# design.net
KiCad netlist of a schematic drawn in EasyEDA Pro
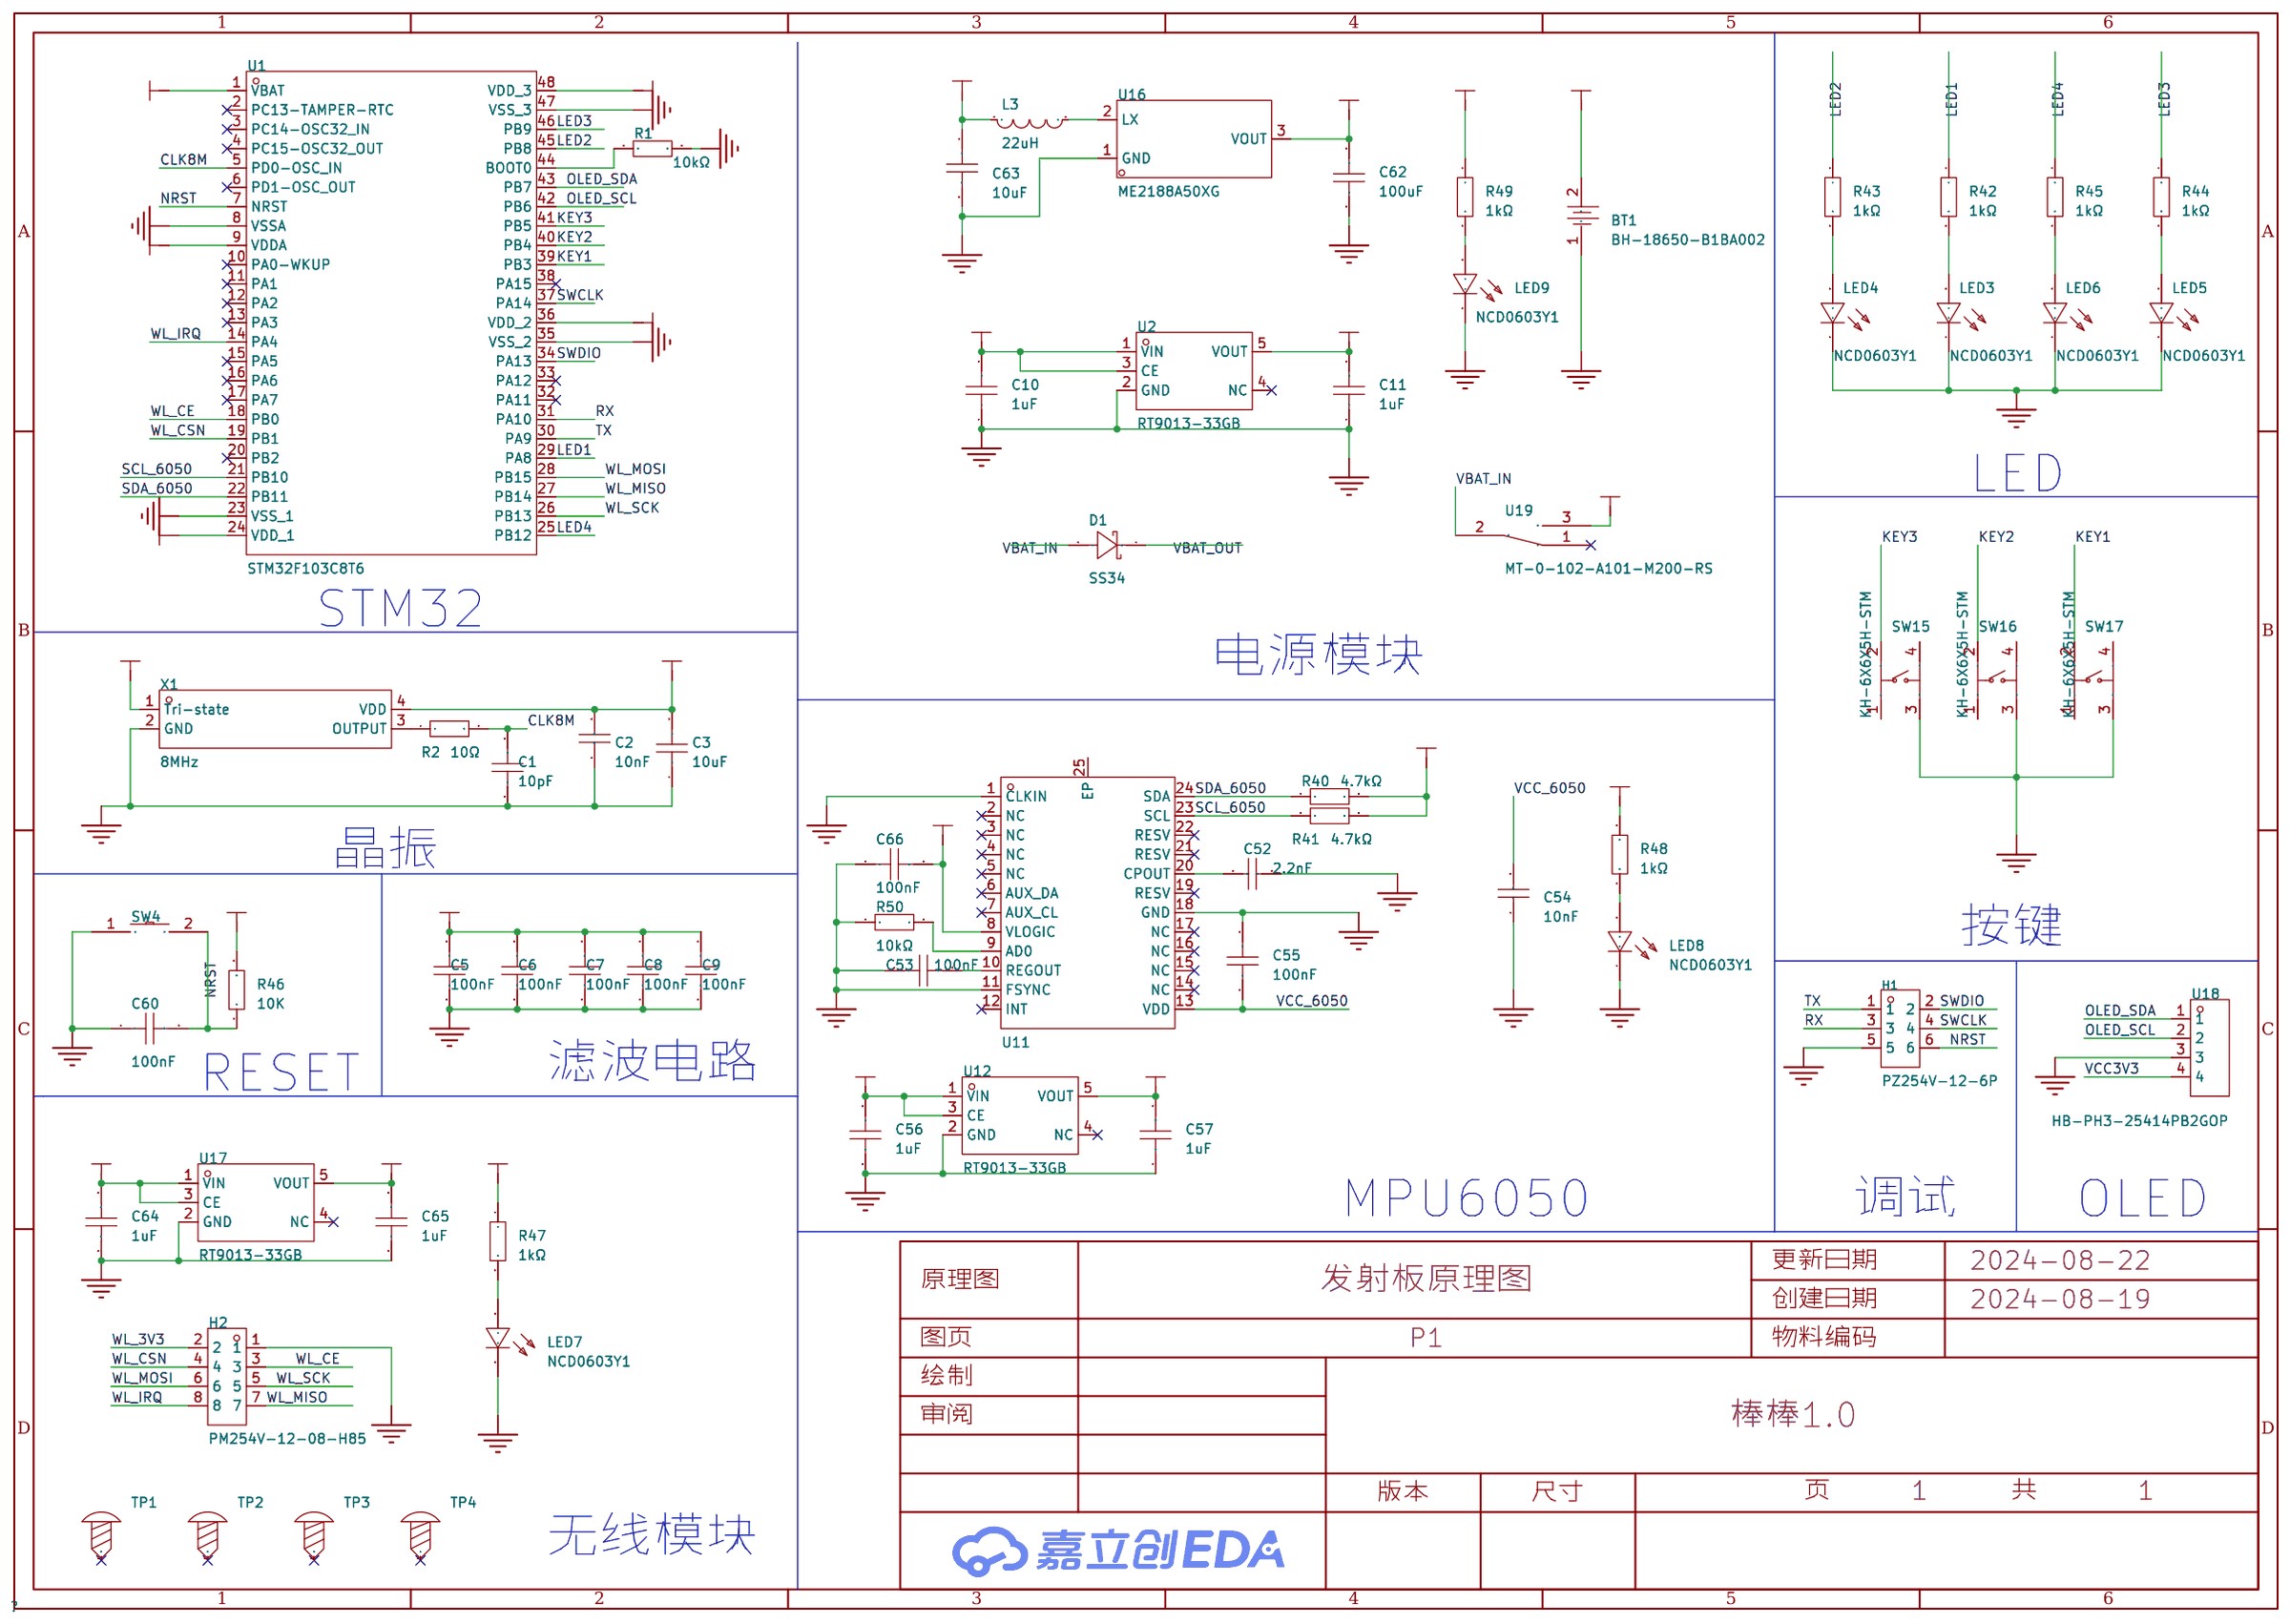
[diagram p0: schematic sheet]

(export (version "E")
  (design (tool "Eeschema 10.0.6"))
  (components
    (comp (ref "BT1")
      (value "BH-18650-B1BA002")
      (footprint "easyedapro:BATTERY-SMD_18650-1S-L77.1-W20.7-1")
      (description "连接器类型:电池盒;适用电池规格:18650;")
      (fields (field (name "Manufacturer") "MYOUNG(美阳)"))
      (libsource (lib "easyedapro") (part "BH-18650-B1BA002"))
    )
    (comp (ref "C1")
      (value "10pF")
      (footprint "easyedapro:C0603")
      (description "容值:10pF;精度:±5%;额定电压:50V;材质(温度系数):C0G;")
      (fields (field (name "Manufacturer Part") "0603CG100J500NT") (field (name "Manufacturer") "FH(风华)"))
      (libsource (lib "easyedapro") (part "0603CG100J500NT"))
    )
    (comp (ref "C2")
      (value "10nF")
      (footprint "easyedapro:C0603")
      (description "容值:10nF;精度:±10%;额定电压:50V;材质(温度系数):X7R;")
      (fields (field (name "Manufacturer Part") "0603B103K500NT") (field (name "Manufacturer") "FH(风华)"))
      (libsource (lib "easyedapro") (part "0603B103K500NT"))
    )
    (comp (ref "C3")
      (value "10uF")
      (footprint "easyedapro:C0603")
      (description "容值:10uF;精度:±10%;额定电压:10V;材质(温度系数):X5R;")
      (fields
        (field (name "Manufacturer Part") "CL10A106KP8NNNC")
        (field (name "Manufacturer") "SAMSUNG(三星)")
      )
      (libsource (lib "easyedapro") (part "CL10A106KP8NNNC"))
    )
    (comp (ref "C5")
      (value "100nF")
      (footprint "easyedapro:C0603")
      (description "容值:100nF;精度:±10%;额定电压:50V;材质(温度系数):X7R;")
      (fields
        (field (name "Manufacturer Part") "CC0603KRX7R9BB104")
        (field (name "Manufacturer") "YAGEO(国巨)")
      )
      (libsource (lib "easyedapro") (part "CC0603KRX7R9BB104"))
    )
    (comp (ref "C6")
      (value "100nF")
      (footprint "easyedapro:C0603")
      (description "容值:100nF;精度:±10%;额定电压:50V;材质(温度系数):X7R;")
      (fields
        (field (name "Manufacturer Part") "CC0603KRX7R9BB104")
        (field (name "Manufacturer") "YAGEO(国巨)")
      )
      (libsource (lib "easyedapro") (part "CC0603KRX7R9BB104"))
    )
    (comp (ref "C7")
      (value "100nF")
      (footprint "easyedapro:C0603")
      (description "容值:100nF;精度:±10%;额定电压:50V;材质(温度系数):X7R;")
      (fields
        (field (name "Manufacturer Part") "CC0603KRX7R9BB104")
        (field (name "Manufacturer") "YAGEO(国巨)")
      )
      (libsource (lib "easyedapro") (part "CC0603KRX7R9BB104"))
    )
    (comp (ref "C8")
      (value "100nF")
      (footprint "easyedapro:C0603")
      (description "容值:100nF;精度:±10%;额定电压:50V;材质(温度系数):X7R;")
      (fields
        (field (name "Manufacturer Part") "CC0603KRX7R9BB104")
        (field (name "Manufacturer") "YAGEO(国巨)")
      )
      (libsource (lib "easyedapro") (part "CC0603KRX7R9BB104"))
    )
    (comp (ref "C9")
      (value "100nF")
      (footprint "easyedapro:C0603")
      (description "容值:100nF;精度:±10%;额定电压:50V;材质(温度系数):X7R;")
      (fields
        (field (name "Manufacturer Part") "CC0603KRX7R9BB104")
        (field (name "Manufacturer") "YAGEO(国巨)")
      )
      (libsource (lib "easyedapro") (part "CC0603KRX7R9BB104"))
    )
    (comp (ref "C10")
      (value "1uF")
      (footprint "easyedapro:C0603")
      (description "容值:1uF;精度:±10%;额定电压:50V;材质(温度系数):X5R;")
      (fields
        (field (name "Manufacturer Part") "CL10A105KB8NNNC")
        (field (name "Manufacturer") "SAMSUNG(三星)")
      )
      (libsource (lib "easyedapro") (part "CL10A105KB8NNNC"))
    )
    (comp (ref "C11")
      (value "1uF")
      (footprint "easyedapro:C0603")
      (description "容值:1uF;精度:±10%;额定电压:50V;材质(温度系数):X5R;")
      (fields
        (field (name "Manufacturer Part") "CL10A105KB8NNNC")
        (field (name "Manufacturer") "SAMSUNG(三星)")
      )
      (libsource (lib "easyedapro") (part "CL10A105KB8NNNC"))
    )
    (comp (ref "C52")
      (value "2.2nF")
      (footprint "easyedapro:C0603")
      (description "容值:2.2nF;精度:±5%;额定电压:50V;材质(温度系数):X7R;")
      (fields (field (name "Manufacturer Part") "0603B222J500NT") (field (name "Manufacturer") "FH(风华)"))
      (libsource (lib "easyedapro") (part "0603B222J500NT"))
    )
    (comp (ref "C53")
      (value "100nF")
      (footprint "easyedapro:C0603")
      (description "容值:100nF;精度:±10%;额定电压:50V;材质(温度系数):X7R;")
      (fields
        (field (name "Manufacturer Part") "CC0603KRX7R9BB104")
        (field (name "Manufacturer") "YAGEO(国巨)")
      )
      (libsource (lib "easyedapro") (part "CC0603KRX7R9BB104"))
    )
    (comp (ref "C54")
      (value "10nF")
      (footprint "easyedapro:C0603")
      (description "容值:10nF;精度:±10%;额定电压:50V;材质(温度系数):X7R;")
      (fields
        (field (name "Manufacturer Part") "CC0603KRX7R9BB103")
        (field (name "Manufacturer") "YAGEO(国巨)")
      )
      (libsource (lib "easyedapro") (part "CC0603KRX7R9BB103"))
    )
    (comp (ref "C55")
      (value "100nF")
      (footprint "easyedapro:C0603")
      (description "容值:100nF;精度:±10%;额定电压:50V;材质(温度系数):X7R;")
      (fields
        (field (name "Manufacturer Part") "CC0603KRX7R9BB104")
        (field (name "Manufacturer") "YAGEO(国巨)")
      )
      (libsource (lib "easyedapro") (part "CC0603KRX7R9BB104"))
    )
    (comp (ref "C56")
      (value "1uF")
      (footprint "easyedapro:C0603")
      (description "容值:1uF;精度:±10%;额定电压:50V;材质(温度系数):X5R;")
      (fields
        (field (name "Manufacturer Part") "CL10A105KB8NNNC")
        (field (name "Manufacturer") "SAMSUNG(三星)")
      )
      (libsource (lib "easyedapro") (part "CL10A105KB8NNNC"))
    )
    (comp (ref "C57")
      (value "1uF")
      (footprint "easyedapro:C0603")
      (description "容值:1uF;精度:±10%;额定电压:50V;材质(温度系数):X5R;")
      (fields
        (field (name "Manufacturer Part") "CL10A105KB8NNNC")
        (field (name "Manufacturer") "SAMSUNG(三星)")
      )
      (libsource (lib "easyedapro") (part "CL10A105KB8NNNC"))
    )
    (comp (ref "C60")
      (value "100nF")
      (footprint "easyedapro:C0603")
      (libsource (lib "easyedapro") (part "CapAcitance"))
    )
    (comp (ref "C62")
      (value "100uF")
      (footprint "easyedapro:C0603")
      (libsource (lib "easyedapro") (part "CapAcitance"))
    )
    (comp (ref "C63")
      (value "10uF")
      (footprint "easyedapro:C0603")
      (libsource (lib "easyedapro") (part "CapAcitance"))
    )
    (comp (ref "C64")
      (value "1uF")
      (footprint "easyedapro:C0603")
      (description "容值:1uF;精度:±10%;额定电压:50V;材质(温度系数):X5R;")
      (fields
        (field (name "Manufacturer Part") "CL10A105KB8NNNC")
        (field (name "Manufacturer") "SAMSUNG(三星)")
      )
      (libsource (lib "easyedapro") (part "CL10A105KB8NNNC"))
    )
    (comp (ref "C65")
      (value "1uF")
      (footprint "easyedapro:C0603")
      (description "容值:1uF;精度:±10%;额定电压:50V;材质(温度系数):X5R;")
      (fields
        (field (name "Manufacturer Part") "CL10A105KB8NNNC")
        (field (name "Manufacturer") "SAMSUNG(三星)")
      )
      (libsource (lib "easyedapro") (part "CL10A105KB8NNNC"))
    )
    (comp (ref "C66")
      (value "100nF")
      (footprint "easyedapro:C0603")
      (description "容值:100nF;精度:±10%;额定电压:50V;材质(温度系数):X7R;")
      (fields
        (field (name "Manufacturer Part") "CC0603KRX7R9BB104")
        (field (name "Manufacturer") "YAGEO(国巨)")
      )
      (libsource (lib "easyedapro") (part "CC0603KRX7R9BB104"))
    )
    (comp (ref "D1")
      (value "SS34")
      (footprint "easyedapro:SMA_L4.3-W2.5-LS5.0-RD")
      (description "二极管配置:独立式;正向压降(Vf):550mV@3A;直流反向耐压(Vr):40V;平均整流电流(Io):3A;")
      (fields (field (name "Manufacturer") "TWGMC(台湾迪嘉)"))
      (libsource (lib "easyedapro") (part "SS34_C727060"))
    )
    (comp (ref "H1")
      (value "PZ254V-12-6P")
      (fields (field (name "Manufacturer") "XFCN(兴飞)"))
      (libsource (lib "easyedapro") (part "PZ254V-12-6P"))
    )
    (comp (ref "H2")
      (value "PM254V-12-08-H85")
      (footprint "easyedapro:HDR-TH_8P-P2.54-V-F-R2-C4-S2.54")
      (fields (field (name "Manufacturer") "XFCN(兴飞)"))
      (libsource (lib "easyedapro") (part "PM254V-12-08-H85_C2834799"))
    )
    (comp (ref "L3")
      (value "22uH")
      (footprint "easyedapro:IND-SMD_L7.1-W6.6")
      (description "电感值:22uH;精度:±20%;额定电流:3A;")
      (fields
        (field (name "Manufacturer Part") "YSPI0630A-220M")
        (field (name "Manufacturer") "YJYCOIN(益嘉源)")
      )
      (libsource (lib "easyedapro") (part "YSPI0630A-220M"))
    )
    (comp (ref "LED3")
      (value "NCD0603Y1")
      (footprint "easyedapro:LED0603-RD")
      (description "发光颜色:黄色;功率:65mW;透镜颜色:无色透明;主波长:586nm~595nm;发光强度:80mcd~220mcd;发光角度:130°;工作温度:-30°C~+85°C;")
      (fields (field (name "Manufacturer") "国星光电"))
      (libsource (lib "easyedapro") (part "FC-D1608HYK-588J"))
    )
    (comp (ref "LED4")
      (value "NCD0603Y1")
      (footprint "easyedapro:LED0603-RD")
      (description "发光颜色:黄色;功率:65mW;透镜颜色:无色透明;主波长:586nm~595nm;发光强度:80mcd~220mcd;发光角度:130°;工作温度:-30°C~+85°C;")
      (fields (field (name "Manufacturer") "国星光电"))
      (libsource (lib "easyedapro") (part "FC-D1608HYK-588J"))
    )
    (comp (ref "LED5")
      (value "NCD0603Y1")
      (footprint "easyedapro:LED0603-RD")
      (description "发光颜色:黄色;功率:65mW;透镜颜色:无色透明;主波长:586nm~595nm;发光强度:80mcd~220mcd;发光角度:130°;工作温度:-30°C~+85°C;")
      (fields (field (name "Manufacturer") "国星光电"))
      (libsource (lib "easyedapro") (part "FC-D1608HYK-588J"))
    )
    (comp (ref "LED6")
      (value "NCD0603Y1")
      (footprint "easyedapro:LED0603-RD")
      (description "发光颜色:黄色;功率:65mW;透镜颜色:无色透明;主波长:586nm~595nm;发光强度:80mcd~220mcd;发光角度:130°;工作温度:-30°C~+85°C;")
      (fields (field (name "Manufacturer") "国星光电"))
      (libsource (lib "easyedapro") (part "FC-D1608HYK-588J"))
    )
    (comp (ref "LED7")
      (value "NCD0603Y1")
      (footprint "easyedapro:LED0603-RD")
      (description "发光颜色:黄色;功率:65mW;透镜颜色:无色透明;主波长:586nm~595nm;发光强度:80mcd~220mcd;发光角度:130°;工作温度:-30°C~+85°C;")
      (fields (field (name "Manufacturer") "国星光电"))
      (libsource (lib "easyedapro") (part "FC-D1608HYK-588J"))
    )
    (comp (ref "LED8")
      (value "NCD0603Y1")
      (footprint "easyedapro:LED0603-RD")
      (description "发光颜色:黄色;功率:65mW;透镜颜色:无色透明;主波长:586nm~595nm;发光强度:80mcd~220mcd;发光角度:130°;工作温度:-30°C~+85°C;")
      (fields (field (name "Manufacturer") "国星光电"))
      (libsource (lib "easyedapro") (part "FC-D1608HYK-588J"))
    )
    (comp (ref "LED9")
      (value "NCD0603Y1")
      (footprint "easyedapro:LED0603-RD")
      (description "发光颜色:黄色;功率:65mW;透镜颜色:无色透明;主波长:586nm~595nm;发光强度:80mcd~220mcd;发光角度:130°;工作温度:-30°C~+85°C;")
      (fields (field (name "Manufacturer") "国星光电"))
      (libsource (lib "easyedapro") (part "FC-D1608HYK-588J"))
    )
    (comp (ref "R1")
      (value "10kΩ")
      (footprint "easyedapro:R0603")
      (description "电阻类型:厚膜电阻;阻值:10kΩ;精度:±1%;功率:100mW;最大工作电压:75V;温度系数:±100ppm/°C;")
      (fields
        (field (name "Manufacturer Part") "0603WAF1002T5E")
        (field (name "Manufacturer") "UNI-ROYAL(厚声)")
      )
      (libsource (lib "easyedapro") (part "0603WAF1002T5E"))
    )
    (comp (ref "R2")
      (value "10Ω")
      (footprint "easyedapro:R0603")
      (description "电阻类型:厚膜电阻;阻值:10Ω;精度:±1%;功率:100mW;最大工作电压:75V;温度系数:±400ppm/°C;")
      (fields
        (field (name "Manufacturer Part") "0603WAF100JT5E")
        (field (name "Manufacturer") "UNI-ROYAL(厚声)")
      )
      (libsource (lib "easyedapro") (part "0603WAF100JT5E"))
    )
    (comp (ref "R40")
      (value "4.7kΩ")
      (footprint "easyedapro:R0603")
      (description "电阻类型:厚膜电阻;阻值:4.7kΩ;精度:±1%;功率:100mW;最大工作电压:75V;温度系数:±100ppm/°C;")
      (fields
        (field (name "Manufacturer Part") "0603WAF4701T5E")
        (field (name "Manufacturer") "UNI-ROYAL(厚声)")
      )
      (libsource (lib "easyedapro") (part "0603WAF4701T5E"))
    )
    (comp (ref "R41")
      (value "4.7kΩ")
      (footprint "easyedapro:R0603")
      (description "电阻类型:厚膜电阻;阻值:4.7kΩ;精度:±1%;功率:100mW;最大工作电压:75V;温度系数:±100ppm/°C;")
      (fields
        (field (name "Manufacturer Part") "0603WAF4701T5E")
        (field (name "Manufacturer") "UNI-ROYAL(厚声)")
      )
      (libsource (lib "easyedapro") (part "0603WAF4701T5E"))
    )
    (comp (ref "R42")
      (value "1kΩ")
      (footprint "easyedapro:R0603")
      (description "电阻类型:厚膜电阻;阻值:1kΩ;精度:±1%;功率:100mW;最大工作电压:75V;温度系数:±100ppm/°C;")
      (fields
        (field (name "Manufacturer Part") "0603WAF1001T5E")
        (field (name "Manufacturer") "UNI-ROYAL(厚声)")
      )
      (libsource (lib "easyedapro") (part "0603WAF1001T5E"))
    )
    (comp (ref "R43")
      (value "1kΩ")
      (footprint "easyedapro:R0603")
      (description "电阻类型:厚膜电阻;阻值:1kΩ;精度:±1%;功率:100mW;最大工作电压:75V;温度系数:±100ppm/°C;")
      (fields
        (field (name "Manufacturer Part") "0603WAF1001T5E")
        (field (name "Manufacturer") "UNI-ROYAL(厚声)")
      )
      (libsource (lib "easyedapro") (part "0603WAF1001T5E"))
    )
    (comp (ref "R44")
      (value "1kΩ")
      (footprint "easyedapro:R0603")
      (description "电阻类型:厚膜电阻;阻值:1kΩ;精度:±1%;功率:100mW;最大工作电压:75V;温度系数:±100ppm/°C;")
      (fields
        (field (name "Manufacturer Part") "0603WAF1001T5E")
        (field (name "Manufacturer") "UNI-ROYAL(厚声)")
      )
      (libsource (lib "easyedapro") (part "0603WAF1001T5E"))
    )
    (comp (ref "R45")
      (value "1kΩ")
      (footprint "easyedapro:R0603")
      (description "电阻类型:厚膜电阻;阻值:1kΩ;精度:±1%;功率:100mW;最大工作电压:75V;温度系数:±100ppm/°C;")
      (fields
        (field (name "Manufacturer Part") "0603WAF1001T5E")
        (field (name "Manufacturer") "UNI-ROYAL(厚声)")
      )
      (libsource (lib "easyedapro") (part "0603WAF1001T5E"))
    )
    (comp (ref "R46") (value "10K") (footprint "easyedapro:R0603") (libsource (lib "easyedapro") (part "电阻")))
    (comp (ref "R47")
      (value "1kΩ")
      (footprint "easyedapro:R0603")
      (description "电阻类型:厚膜电阻;阻值:1kΩ;精度:±1%;功率:100mW;最大工作电压:75V;温度系数:±100ppm/°C;")
      (fields
        (field (name "Manufacturer Part") "0603WAF1001T5E")
        (field (name "Manufacturer") "UNI-ROYAL(厚声)")
      )
      (libsource (lib "easyedapro") (part "0603WAF1001T5E"))
    )
    (comp (ref "R48")
      (value "1kΩ")
      (footprint "easyedapro:R0603")
      (description "电阻类型:厚膜电阻;阻值:1kΩ;精度:±1%;功率:100mW;最大工作电压:75V;温度系数:±100ppm/°C;")
      (fields
        (field (name "Manufacturer Part") "0603WAF1001T5E")
        (field (name "Manufacturer") "UNI-ROYAL(厚声)")
      )
      (libsource (lib "easyedapro") (part "0603WAF1001T5E"))
    )
    (comp (ref "R49")
      (value "1kΩ")
      (footprint "easyedapro:R0603")
      (description "电阻类型:厚膜电阻;阻值:1kΩ;精度:±1%;功率:100mW;最大工作电压:75V;温度系数:±100ppm/°C;")
      (fields
        (field (name "Manufacturer Part") "0603WAF1001T5E")
        (field (name "Manufacturer") "UNI-ROYAL(厚声)")
      )
      (libsource (lib "easyedapro") (part "0603WAF1001T5E"))
    )
    (comp (ref "R50")
      (value "10kΩ")
      (footprint "easyedapro:R0603")
      (description "电阻类型:厚膜电阻;阻值:10kΩ;精度:±1%;功率:100mW;最大工作电压:75V;温度系数:±100ppm/°C;")
      (fields
        (field (name "Manufacturer Part") "0603WAF1002T5E")
        (field (name "Manufacturer") "UNI-ROYAL(厚声)")
      )
      (libsource (lib "easyedapro") (part "0603WAF1002T5E"))
    )
    (comp (ref "SW4")
      (value "TS-1101-C-W")
      (footprint "easyedapro:SW-SMD_L6.0-W3.3-LS8.0")
      (fields (field (name "Manufacturer") "XKB Connectivity(中国星坤)"))
      (libsource (lib "easyedapro") (part "TS-1101-C-W"))
    )
    (comp (ref "SW15")
      (value "KH-6X6X5H-STM")
      (footprint "easyedapro:SW-SMD_4P-L6.0-W6.0-P4.50-LS9.0-2")
      (description "电路结构:单刀单掷;按钮形状:圆形按钮;安装方式:立贴;开关长度:6mm;开关宽度:6mm;开关高度:5mm;带支架:不带;触点电流:50mA;额定电压(DC):12V;机械寿命:8万次;")
      (fields (field (name "Manufacturer") "kinghelm(金航标)"))
      (libsource (lib "easyedapro") (part "KH-6X6X5H-STM"))
    )
    (comp (ref "SW16")
      (value "KH-6X6X5H-STM")
      (footprint "easyedapro:SW-SMD_4P-L6.0-W6.0-P4.50-LS9.0-2")
      (description "电路结构:单刀单掷;按钮形状:圆形按钮;安装方式:立贴;开关长度:6mm;开关宽度:6mm;开关高度:5mm;带支架:不带;触点电流:50mA;额定电压(DC):12V;机械寿命:8万次;")
      (fields (field (name "Manufacturer") "kinghelm(金航标)"))
      (libsource (lib "easyedapro") (part "KH-6X6X5H-STM"))
    )
    (comp (ref "SW17")
      (value "KH-6X6X5H-STM")
      (footprint "easyedapro:SW-SMD_4P-L6.0-W6.0-P4.50-LS9.0-2")
      (description "电路结构:单刀单掷;按钮形状:圆形按钮;安装方式:立贴;开关长度:6mm;开关宽度:6mm;开关高度:5mm;带支架:不带;触点电流:50mA;额定电压(DC):12V;机械寿命:8万次;")
      (fields (field (name "Manufacturer") "kinghelm(金航标)"))
      (libsource (lib "easyedapro") (part "KH-6X6X5H-STM"))
    )
    (comp (ref "TP1") (value "~") (footprint "easyedapro:M3螺丝") (libsource (lib "easyedapro") (part "螺丝孔")))
    (comp (ref "TP2") (value "~") (footprint "easyedapro:M3螺丝") (libsource (lib "easyedapro") (part "螺丝孔")))
    (comp (ref "TP3") (value "~") (footprint "easyedapro:M3螺丝") (libsource (lib "easyedapro") (part "螺丝孔")))
    (comp (ref "TP4") (value "~") (footprint "easyedapro:M3螺丝") (libsource (lib "easyedapro") (part "螺丝孔")))
    (comp (ref "U1")
      (value "STM32F103C8T6")
      (footprint "easyedapro:LQFP-48_L7.0-W7.0-P0.50-LS9.0-BL")
      (fields (field (name "Manufacturer") "ST(意法半导体)"))
      (libsource (lib "easyedapro") (part "STM32F103C8T6"))
    )
    (comp (ref "U2")
      (value "RT9013-33GB")
      (footprint "easyedapro:SOT-23-5_L2.9-W1.6-P0.95-LS2.8-BR")
      (fields (field (name "Manufacturer") "TECH PUBLIC(台舟)"))
      (libsource (lib "easyedapro") (part "RT9013-33GB_C19268157"))
    )
    (comp (ref "U11")
      (value "MPU-6050")
      (footprint "easyedapro:QFN-24_L4.0-W4.0-P0.50-BL-EP2.7")
      (description "传感器类型:加速度计陀螺仪;")
      (fields (field (name "Manufacturer") "TDK InvenSense(应美盛)"))
      (libsource (lib "easyedapro") (part "MPU-6050_C24112"))
    )
    (comp (ref "U12")
      (value "RT9013-33GB")
      (footprint "easyedapro:SOT-23-5_L2.9-W1.6-P0.95-LS2.8-BR")
      (fields (field (name "Manufacturer") "TECH PUBLIC(台舟)"))
      (libsource (lib "easyedapro") (part "RT9013-33GB_C19268157"))
    )
    (comp (ref "U16")
      (value "ME2188A50XG")
      (footprint "easyedapro:SOT-23-3_L2.9-W1.6-P1.90-LS2.8-BR")
      (description "功能类型:升压型;输入电压:900mV~5V;输出电压:5V;输出电流(最大值):300mA;")
      (fields (field (name "Manufacturer") "MICRONE(南京微盟)"))
      (libsource (lib "easyedapro") (part "ME2188A50XG"))
    )
    (comp (ref "U17")
      (value "RT9013-33GB")
      (footprint "easyedapro:SOT-23-5_L2.9-W1.6-P0.95-LS2.8-BR")
      (fields (field (name "Manufacturer") "TECH PUBLIC(台舟)"))
      (libsource (lib "easyedapro") (part "RT9013-33GB_C19268157"))
    )
    (comp (ref "U18")
      (value "HB-PH3-25414PB2GOP")
      (footprint "easyedapro:HDR-TH_4P-P2.54-V-M")
      (fields (field (name "Manufacturer") "HANBO(汉博)"))
      (libsource (lib "easyedapro") (part "HB-PH3-25414PB2GOP"))
    )
    (comp (ref "U19")
      (value "MT-0-102-A101-M200-RS")
      (footprint "easyedapro:SW-TH_MT-0-103-A101-M200-RS")
      (description "电路结构:单刀双掷;机械寿命:-;额定电流:5A;额定电压(AC):125V;安装方式:直插;")
      (fields (field (name "Manufacturer") "YUEN FUNG(源丰)"))
      (libsource (lib "easyedapro") (part "MT-0-102-A101-M200-RS+PJ"))
    )
    (comp (ref "X1")
      (value "8MHz")
      (footprint "easyedapro:OSC-SMD_4P-L3.2-W2.5-BL_SIT8008BI")
      (description "频率:8MHz;工作电压:3.3V;输出模式:CMOS;频率稳定度:±20ppm;")
      (fields
        (field (name "Manufacturer Part") "S3D8.000000B20F30T")
        (field (name "Manufacturer") "SCTF(星通时频)")
      )
      (libsource (lib "easyedapro") (part "S3D8.000000B20F30T"))
    )
  )
  (nets
    (net (code "1") (name "/CLK8M") (class "Default")
      (node (ref "C1") (pin "2") (pinfunction "2_2") (pintype "unspecified"))
      (node (ref "R2") (pin "2") (pinfunction "2_2") (pintype "input"))
      (node (ref "U1") (pin "5") (pinfunction "PD0-OSC_IN_5") (pintype "unspecified"))
    )
    (net (code "2") (name "/KEY1") (class "Default")
      (node (ref "SW17") (pin "2") (pinfunction "2_2") (pintype "unspecified"))
      (node (ref "U1") (pin "39") (pinfunction "PB3_39") (pintype "unspecified"))
    )
    (net (code "3") (name "/KEY2") (class "Default")
      (node (ref "SW16") (pin "2") (pinfunction "2_2") (pintype "unspecified"))
      (node (ref "U1") (pin "40") (pinfunction "PB4_40") (pintype "unspecified"))
    )
    (net (code "4") (name "/KEY3") (class "Default")
      (node (ref "SW15") (pin "2") (pinfunction "2_2") (pintype "unspecified"))
      (node (ref "U1") (pin "41") (pinfunction "PB5_41") (pintype "unspecified"))
    )
    (net (code "5") (name "/LED1") (class "Default")
      (node (ref "R42") (pin "1") (pinfunction "1_1") (pintype "input"))
      (node (ref "U1") (pin "29") (pinfunction "PA8_29") (pintype "unspecified"))
    )
    (net (code "6") (name "/LED2") (class "Default")
      (node (ref "R43") (pin "1") (pinfunction "1_1") (pintype "input"))
      (node (ref "U1") (pin "45") (pinfunction "PB8_45") (pintype "unspecified"))
    )
    (net (code "7") (name "/LED3") (class "Default")
      (node (ref "R44") (pin "1") (pinfunction "1_1") (pintype "input"))
      (node (ref "U1") (pin "46") (pinfunction "PB9_46") (pintype "unspecified"))
    )
    (net (code "8") (name "/LED4") (class "Default")
      (node (ref "R45") (pin "1") (pinfunction "1_1") (pintype "input"))
      (node (ref "U1") (pin "25") (pinfunction "PB12_25") (pintype "unspecified"))
    )
    (net (code "9") (name "/NRST") (class "Default")
      (node (ref "C60") (pin "2") (pinfunction "2_2") (pintype "input"))
      (node (ref "H1") (pin "6") (pinfunction "6_6") (pintype "input"))
      (node (ref "R46") (pin "1") (pinfunction "1_1") (pintype "input"))
      (node (ref "SW4") (pin "2") (pinfunction "2_2") (pintype "unspecified"))
      (node (ref "U1") (pin "7") (pinfunction "NRST_7") (pintype "unspecified"))
    )
    (net (code "10") (name "/OLED_SCL") (class "Default")
      (node (ref "U1") (pin "42") (pinfunction "PB6_42") (pintype "unspecified"))
      (node (ref "U18") (pin "2") (pinfunction "2_2") (pintype "unspecified"))
    )
    (net (code "11") (name "/OLED_SDA") (class "Default")
      (node (ref "U1") (pin "43") (pinfunction "PB7_43") (pintype "unspecified"))
      (node (ref "U18") (pin "1") (pinfunction "1_1") (pintype "unspecified"))
    )
    (net (code "12") (name "/RX") (class "Default")
      (node (ref "H1") (pin "3") (pinfunction "3_3") (pintype "input"))
      (node (ref "U1") (pin "31") (pinfunction "PA10_31") (pintype "unspecified"))
    )
    (net (code "13") (name "/SCL_6050") (class "Default")
      (node (ref "R41") (pin "1") (pinfunction "1_1") (pintype "input"))
      (node (ref "U1") (pin "21") (pinfunction "PB10_21") (pintype "unspecified"))
      (node (ref "U11") (pin "23") (pinfunction "SCL_23") (pintype "unspecified"))
    )
    (net (code "14") (name "/SDA_6050") (class "Default")
      (node (ref "R40") (pin "1") (pinfunction "1_1") (pintype "input"))
      (node (ref "U1") (pin "22") (pinfunction "PB11_22") (pintype "unspecified"))
      (node (ref "U11") (pin "24") (pinfunction "SDA_24") (pintype "unspecified"))
    )
    (net (code "15") (name "/SWCLK") (class "Default")
      (node (ref "H1") (pin "4") (pinfunction "4_4") (pintype "input"))
      (node (ref "U1") (pin "37") (pinfunction "PA14_37") (pintype "unspecified"))
    )
    (net (code "16") (name "/SWDIO") (class "Default")
      (node (ref "H1") (pin "2") (pinfunction "2_2") (pintype "input"))
      (node (ref "U1") (pin "34") (pinfunction "PA13_34") (pintype "unspecified"))
    )
    (net (code "17") (name "/TX") (class "Default")
      (node (ref "H1") (pin "1") (pinfunction "1_1") (pintype "input"))
      (node (ref "U1") (pin "30") (pinfunction "PA9_30") (pintype "unspecified"))
    )
    (net (code "18") (name "/VBAT_IN") (class "Default")
      (node (ref "D1") (pin "2") (pinfunction "A_2") (pintype "unspecified"))
      (node (ref "U19") (pin "2") (pinfunction "2_2") (pintype "unspecified"))
    )
    (net (code "19") (name "/WL_CE") (class "Default")
      (node (ref "H2") (pin "3") (pinfunction "3_3") (pintype "unspecified"))
      (node (ref "U1") (pin "18") (pinfunction "PB0_18") (pintype "unspecified"))
    )
    (net (code "20") (name "/WL_CSN") (class "Default")
      (node (ref "H2") (pin "4") (pinfunction "4_4") (pintype "unspecified"))
      (node (ref "U1") (pin "19") (pinfunction "PB1_19") (pintype "unspecified"))
    )
    (net (code "21") (name "/WL_IRQ") (class "Default")
      (node (ref "H2") (pin "8") (pinfunction "8_8") (pintype "unspecified"))
      (node (ref "U1") (pin "14") (pinfunction "PA4_14") (pintype "unspecified"))
    )
    (net (code "22") (name "/WL_MISO") (class "Default")
      (node (ref "H2") (pin "7") (pinfunction "7_7") (pintype "unspecified"))
      (node (ref "U1") (pin "27") (pinfunction "PB14_27") (pintype "unspecified"))
    )
    (net (code "23") (name "/WL_MOSI") (class "Default")
      (node (ref "H2") (pin "6") (pinfunction "6_6") (pintype "unspecified"))
      (node (ref "U1") (pin "28") (pinfunction "PB15_28") (pintype "unspecified"))
    )
    (net (code "24") (name "/WL_SCK") (class "Default")
      (node (ref "H2") (pin "5") (pinfunction "5_5") (pintype "unspecified"))
      (node (ref "U1") (pin "26") (pinfunction "PB13_26") (pintype "unspecified"))
    )
    (net (code "25") (name "GND") (class "Default")
      (node (ref "BT1") (pin "1") (pinfunction "1_1") (pintype "input"))
      (node (ref "C1") (pin "1") (pinfunction "1_1") (pintype "unspecified"))
      (node (ref "C10") (pin "1") (pinfunction "1_1") (pintype "unspecified"))
      (node (ref "C11") (pin "1") (pinfunction "1_1") (pintype "unspecified"))
      (node (ref "C2") (pin "1") (pinfunction "1_1") (pintype "input"))
      (node (ref "C3") (pin "1") (pinfunction "1_1") (pintype "unspecified"))
      (node (ref "C5") (pin "1") (pinfunction "1_1") (pintype "unspecified"))
      (node (ref "C52") (pin "2") (pinfunction "2_2") (pintype "input"))
      (node (ref "C53") (pin "1") (pinfunction "1_1") (pintype "unspecified"))
      (node (ref "C54") (pin "1") (pinfunction "1_1") (pintype "input"))
      (node (ref "C55") (pin "2") (pinfunction "2_2") (pintype "unspecified"))
      (node (ref "C56") (pin "1") (pinfunction "1_1") (pintype "unspecified"))
      (node (ref "C57") (pin "1") (pinfunction "1_1") (pintype "unspecified"))
      (node (ref "C6") (pin "1") (pinfunction "1_1") (pintype "unspecified"))
      (node (ref "C60") (pin "1") (pinfunction "1_1") (pintype "input"))
      (node (ref "C62") (pin "1") (pinfunction "1_1") (pintype "input"))
      (node (ref "C63") (pin "2") (pinfunction "2_2") (pintype "input"))
      (node (ref "C64") (pin "1") (pinfunction "1_1") (pintype "unspecified"))
      (node (ref "C65") (pin "1") (pinfunction "1_1") (pintype "unspecified"))
      (node (ref "C66") (pin "1") (pinfunction "1_1") (pintype "unspecified"))
      (node (ref "C7") (pin "1") (pinfunction "1_1") (pintype "unspecified"))
      (node (ref "C8") (pin "1") (pinfunction "1_1") (pintype "unspecified"))
      (node (ref "C9") (pin "1") (pinfunction "1_1") (pintype "unspecified"))
      (node (ref "H1") (pin "5") (pinfunction "5_5") (pintype "input"))
      (node (ref "H2") (pin "1") (pinfunction "1_1") (pintype "unspecified"))
      (node (ref "LED3") (pin "1") (pinfunction "K_1") (pintype "input"))
      (node (ref "LED4") (pin "1") (pinfunction "K_1") (pintype "input"))
      (node (ref "LED5") (pin "1") (pinfunction "K_1") (pintype "input"))
      (node (ref "LED6") (pin "1") (pinfunction "K_1") (pintype "input"))
      (node (ref "LED7") (pin "1") (pinfunction "K_1") (pintype "input"))
      (node (ref "LED8") (pin "1") (pinfunction "K_1") (pintype "input"))
      (node (ref "LED9") (pin "1") (pinfunction "K_1") (pintype "input"))
      (node (ref "R1") (pin "2") (pinfunction "2_2") (pintype "input"))
      (node (ref "R50") (pin "1") (pinfunction "1_1") (pintype "input"))
      (node (ref "SW15") (pin "3") (pinfunction "3_3") (pintype "unspecified"))
      (node (ref "SW16") (pin "3") (pinfunction "3_3") (pintype "unspecified"))
      (node (ref "SW17") (pin "3") (pinfunction "3_3") (pintype "unspecified"))
      (node (ref "SW4") (pin "1") (pinfunction "1_1") (pintype "unspecified"))
      (node (ref "U1") (pin "23") (pinfunction "VSS_1_23") (pintype "unspecified"))
      (node (ref "U1") (pin "35") (pinfunction "VSS_2_35") (pintype "unspecified"))
      (node (ref "U1") (pin "47") (pinfunction "VSS_3_47") (pintype "unspecified"))
      (node (ref "U1") (pin "8") (pinfunction "VSSA_8") (pintype "unspecified"))
      (node (ref "U11") (pin "1") (pinfunction "CLKIN_1") (pintype "unspecified"))
      (node (ref "U11") (pin "11") (pinfunction "FSYNC_11") (pintype "unspecified"))
      (node (ref "U11") (pin "18") (pinfunction "GND_18") (pintype "unspecified"))
      (node (ref "U12") (pin "2") (pinfunction "GND_2") (pintype "unspecified"))
      (node (ref "U16") (pin "1") (pinfunction "GND_1") (pintype "input"))
      (node (ref "U17") (pin "2") (pinfunction "GND_2") (pintype "unspecified"))
      (node (ref "U18") (pin "3") (pinfunction "3_3") (pintype "unspecified"))
      (node (ref "U2") (pin "2") (pinfunction "GND_2") (pintype "unspecified"))
      (node (ref "X1") (pin "2") (pinfunction "GND_2") (pintype "unspecified"))
    )
    (net (code "26") (name "Net-(LED3-A)") (class "Default")
      (node (ref "LED3") (pin "2") (pinfunction "A_2") (pintype "input"))
      (node (ref "R42") (pin "2") (pinfunction "2_2") (pintype "input"))
    )
    (net (code "27") (name "Net-(LED4-A)") (class "Default")
      (node (ref "LED4") (pin "2") (pinfunction "A_2") (pintype "input"))
      (node (ref "R43") (pin "2") (pinfunction "2_2") (pintype "input"))
    )
    (net (code "28") (name "Net-(LED5-A)") (class "Default")
      (node (ref "LED5") (pin "2") (pinfunction "A_2") (pintype "input"))
      (node (ref "R44") (pin "2") (pinfunction "2_2") (pintype "input"))
    )
    (net (code "29") (name "Net-(LED6-A)") (class "Default")
      (node (ref "LED6") (pin "2") (pinfunction "A_2") (pintype "input"))
      (node (ref "R45") (pin "2") (pinfunction "2_2") (pintype "input"))
    )
    (net (code "30") (name "Net-(LED7-A)") (class "Default")
      (node (ref "LED7") (pin "2") (pinfunction "A_2") (pintype "input"))
      (node (ref "R47") (pin "2") (pinfunction "2_2") (pintype "input"))
    )
    (net (code "31") (name "Net-(LED8-A)") (class "Default")
      (node (ref "LED8") (pin "2") (pinfunction "A_2") (pintype "input"))
      (node (ref "R48") (pin "1") (pinfunction "1_1") (pintype "input"))
    )
    (net (code "32") (name "Net-(LED9-A)") (class "Default")
      (node (ref "LED9") (pin "2") (pinfunction "A_2") (pintype "input"))
      (node (ref "R49") (pin "2") (pinfunction "2_2") (pintype "input"))
    )
    (net (code "33") (name "Net-(U1-BOOT0)") (class "Default")
      (node (ref "R1") (pin "1") (pinfunction "1_1") (pintype "input"))
      (node (ref "U1") (pin "44") (pinfunction "BOOT0_44") (pintype "unspecified"))
    )
    (net (code "34") (name "Net-(U11-AD0)") (class "Default")
      (node (ref "R50") (pin "2") (pinfunction "2_2") (pintype "input"))
      (node (ref "U11") (pin "9") (pinfunction "AD0_9") (pintype "unspecified"))
    )
    (net (code "35") (name "Net-(U11-CPOUT)") (class "Default")
      (node (ref "C52") (pin "1") (pinfunction "1_1") (pintype "input"))
      (node (ref "U11") (pin "20") (pinfunction "CPOUT_20") (pintype "unspecified"))
    )
    (net (code "36") (name "Net-(U11-REGOUT)") (class "Default")
      (node (ref "C53") (pin "2") (pinfunction "2_2") (pintype "unspecified"))
      (node (ref "U11") (pin "10") (pinfunction "REGOUT_10") (pintype "unspecified"))
    )
    (net (code "37") (name "Net-(U16-LX)") (class "Default")
      (node (ref "L3") (pin "2") (pinfunction "2_2") (pintype "unspecified"))
      (node (ref "U16") (pin "2") (pinfunction "LX_2") (pintype "input"))
    )
    (net (code "38") (name "Net-(X1-OUTPUT)") (class "Default")
      (node (ref "R2") (pin "1") (pinfunction "1_1") (pintype "input"))
      (node (ref "X1") (pin "3") (pinfunction "OUTPUT_3") (pintype "unspecified"))
    )
    (net (code "39") (name "PIVCC5V") (class "Default")
      (node (ref "C10") (pin "2") (pinfunction "2_2") (pintype "unspecified"))
      (node (ref "C56") (pin "2") (pinfunction "2_2") (pintype "unspecified"))
      (node (ref "C62") (pin "2") (pinfunction "2_2") (pintype "input"))
      (node (ref "C64") (pin "2") (pinfunction "2_2") (pintype "unspecified"))
      (node (ref "U12") (pin "1") (pinfunction "VIN_1") (pintype "unspecified"))
      (node (ref "U12") (pin "3") (pinfunction "CE_3") (pintype "unspecified"))
      (node (ref "U16") (pin "3") (pinfunction "VOUT_3") (pintype "input"))
      (node (ref "U17") (pin "1") (pinfunction "VIN_1") (pintype "unspecified"))
      (node (ref "U17") (pin "3") (pinfunction "CE_3") (pintype "unspecified"))
      (node (ref "U2") (pin "1") (pinfunction "VIN_1") (pintype "unspecified"))
      (node (ref "U2") (pin "3") (pinfunction "CE_3") (pintype "unspecified"))
    )
    (net (code "40") (name "VBAT") (class "Default")
      (node (ref "BT1") (pin "2") (pinfunction "2_2") (pintype "input"))
      (node (ref "U19") (pin "3") (pinfunction "3_3") (pintype "unspecified"))
    )
    (net (code "41") (name "VBAT_OUT") (class "Default")
      (node (ref "C63") (pin "1") (pinfunction "1_1") (pintype "input"))
      (node (ref "D1") (pin "1") (pinfunction "C_1") (pintype "unspecified"))
      (node (ref "L3") (pin "1") (pinfunction "1_1") (pintype "unspecified"))
    )
    (net (code "42") (name "VCC3V3") (class "Default")
      (node (ref "C11") (pin "2") (pinfunction "2_2") (pintype "unspecified"))
      (node (ref "C2") (pin "2") (pinfunction "2_2") (pintype "input"))
      (node (ref "C3") (pin "2") (pinfunction "2_2") (pintype "unspecified"))
      (node (ref "C5") (pin "2") (pinfunction "2_2") (pintype "unspecified"))
      (node (ref "C6") (pin "2") (pinfunction "2_2") (pintype "unspecified"))
      (node (ref "C7") (pin "2") (pinfunction "2_2") (pintype "unspecified"))
      (node (ref "C8") (pin "2") (pinfunction "2_2") (pintype "unspecified"))
      (node (ref "C9") (pin "2") (pinfunction "2_2") (pintype "unspecified"))
      (node (ref "R46") (pin "2") (pinfunction "2_2") (pintype "input"))
      (node (ref "R49") (pin "1") (pinfunction "1_1") (pintype "input"))
      (node (ref "U1") (pin "1") (pinfunction "VBAT_1") (pintype "unspecified"))
      (node (ref "U1") (pin "24") (pinfunction "VDD_1_24") (pintype "unspecified"))
      (node (ref "U1") (pin "36") (pinfunction "VDD_2_36") (pintype "unspecified"))
      (node (ref "U1") (pin "48") (pinfunction "VDD_3_48") (pintype "unspecified"))
      (node (ref "U1") (pin "9") (pinfunction "VDDA_9") (pintype "unspecified"))
      (node (ref "U18") (pin "4") (pinfunction "4_4") (pintype "unspecified"))
      (node (ref "U2") (pin "5") (pinfunction "VOUT_5") (pintype "unspecified"))
      (node (ref "X1") (pin "1") (pinfunction "Tri-state_1") (pintype "unspecified"))
      (node (ref "X1") (pin "4") (pinfunction "VDD_4") (pintype "unspecified"))
    )
    (net (code "43") (name "VCC_6050") (class "Default")
      (node (ref "C54") (pin "2") (pinfunction "2_2") (pintype "input"))
      (node (ref "C55") (pin "1") (pinfunction "1_1") (pintype "unspecified"))
      (node (ref "C57") (pin "2") (pinfunction "2_2") (pintype "unspecified"))
      (node (ref "C66") (pin "2") (pinfunction "2_2") (pintype "unspecified"))
      (node (ref "R40") (pin "2") (pinfunction "2_2") (pintype "input"))
      (node (ref "R41") (pin "2") (pinfunction "2_2") (pintype "input"))
      (node (ref "R48") (pin "2") (pinfunction "2_2") (pintype "input"))
      (node (ref "U11") (pin "13") (pinfunction "VDD_13") (pintype "unspecified"))
      (node (ref "U11") (pin "8") (pinfunction "VLOGIC_8") (pintype "unspecified"))
      (node (ref "U12") (pin "5") (pinfunction "VOUT_5") (pintype "unspecified"))
    )
    (net (code "44") (name "WL_3V3") (class "Default")
      (node (ref "C65") (pin "2") (pinfunction "2_2") (pintype "unspecified"))
      (node (ref "H2") (pin "2") (pinfunction "2_2") (pintype "unspecified"))
      (node (ref "R47") (pin "1") (pinfunction "1_1") (pintype "input"))
      (node (ref "U17") (pin "5") (pinfunction "VOUT_5") (pintype "unspecified"))
    )
    (net (code "45") (name "unconnected-(SW15-Pad1)") (class "Default")
      (node (ref "SW15") (pin "1") (pinfunction "1_1") (pintype "unspecified"))
    )
    (net (code "46") (name "unconnected-(SW15-Pad4)") (class "Default")
      (node (ref "SW15") (pin "4") (pinfunction "4_4") (pintype "unspecified"))
    )
    (net (code "47") (name "unconnected-(SW16-Pad1)") (class "Default")
      (node (ref "SW16") (pin "1") (pinfunction "1_1") (pintype "unspecified"))
    )
    (net (code "48") (name "unconnected-(SW16-Pad4)") (class "Default")
      (node (ref "SW16") (pin "4") (pinfunction "4_4") (pintype "unspecified"))
    )
    (net (code "49") (name "unconnected-(SW17-Pad1)") (class "Default")
      (node (ref "SW17") (pin "1") (pinfunction "1_1") (pintype "unspecified"))
    )
    (net (code "50") (name "unconnected-(SW17-Pad4)") (class "Default")
      (node (ref "SW17") (pin "4") (pinfunction "4_4") (pintype "unspecified"))
    )
    (net (code "51") (name "unconnected-(TP1-Pad1)") (class "Default")
      (node (ref "TP1") (pin "1") (pinfunction "1_1") (pintype "input+no_connect"))
    )
    (net (code "52") (name "unconnected-(TP2-Pad1)") (class "Default")
      (node (ref "TP2") (pin "1") (pinfunction "1_1") (pintype "input+no_connect"))
    )
    (net (code "53") (name "unconnected-(TP3-Pad1)") (class "Default")
      (node (ref "TP3") (pin "1") (pinfunction "1_1") (pintype "input+no_connect"))
    )
    (net (code "54") (name "unconnected-(TP4-Pad1)") (class "Default")
      (node (ref "TP4") (pin "1") (pinfunction "1_1") (pintype "input+no_connect"))
    )
    (net (code "55") (name "unconnected-(U1-PA0-WKUP-Pad10)") (class "Default")
      (node (ref "U1") (pin "10") (pinfunction "PA0-WKUP_10") (pintype "unspecified+no_connect"))
    )
    (net (code "56") (name "unconnected-(U1-PA1-Pad11)") (class "Default")
      (node (ref "U1") (pin "11") (pinfunction "PA1_11") (pintype "unspecified+no_connect"))
    )
    (net (code "57") (name "unconnected-(U1-PA2-Pad12)") (class "Default")
      (node (ref "U1") (pin "12") (pinfunction "PA2_12") (pintype "unspecified+no_connect"))
    )
    (net (code "58") (name "unconnected-(U1-PA3-Pad13)") (class "Default")
      (node (ref "U1") (pin "13") (pinfunction "PA3_13") (pintype "unspecified+no_connect"))
    )
    (net (code "59") (name "unconnected-(U1-PA5-Pad15)") (class "Default")
      (node (ref "U1") (pin "15") (pinfunction "PA5_15") (pintype "unspecified+no_connect"))
    )
    (net (code "60") (name "unconnected-(U1-PA6-Pad16)") (class "Default")
      (node (ref "U1") (pin "16") (pinfunction "PA6_16") (pintype "unspecified+no_connect"))
    )
    (net (code "61") (name "unconnected-(U1-PA7-Pad17)") (class "Default")
      (node (ref "U1") (pin "17") (pinfunction "PA7_17") (pintype "unspecified+no_connect"))
    )
    (net (code "62") (name "unconnected-(U1-PA11-Pad32)") (class "Default")
      (node (ref "U1") (pin "32") (pinfunction "PA11_32") (pintype "unspecified+no_connect"))
    )
    (net (code "63") (name "unconnected-(U1-PA12-Pad33)") (class "Default")
      (node (ref "U1") (pin "33") (pinfunction "PA12_33") (pintype "unspecified+no_connect"))
    )
    (net (code "64") (name "unconnected-(U1-PA15-Pad38)") (class "Default")
      (node (ref "U1") (pin "38") (pinfunction "PA15_38") (pintype "unspecified+no_connect"))
    )
    (net (code "65") (name "unconnected-(U1-PB2-Pad20)") (class "Default")
      (node (ref "U1") (pin "20") (pinfunction "PB2_20") (pintype "unspecified+no_connect"))
    )
    (net (code "66") (name "unconnected-(U1-PC13-TAMPER-RTC-Pad2)") (class "Default")
      (node (ref "U1") (pin "2") (pinfunction "PC13-TAMPER-RTC_2") (pintype "unspecified+no_connect"))
    )
    (net (code "67") (name "unconnected-(U1-PC14-OSC32_IN-Pad3)") (class "Default")
      (node (ref "U1") (pin "3") (pinfunction "PC14-OSC32_IN_3") (pintype "unspecified+no_connect"))
    )
    (net (code "68") (name "unconnected-(U1-PC15-OSC32_OUT-Pad4)") (class "Default")
      (node (ref "U1") (pin "4") (pinfunction "PC15-OSC32_OUT_4") (pintype "unspecified+no_connect"))
    )
    (net (code "69") (name "unconnected-(U1-PD1-OSC_OUT-Pad6)") (class "Default")
      (node (ref "U1") (pin "6") (pinfunction "PD1-OSC_OUT_6") (pintype "unspecified+no_connect"))
    )
    (net (code "70") (name "unconnected-(U2-NC-Pad4)") (class "Default")
      (node (ref "U2") (pin "4") (pinfunction "NC_4") (pintype "unspecified+no_connect"))
    )
    (net (code "71") (name "unconnected-(U11-AUX_CL-Pad7)") (class "Default")
      (node (ref "U11") (pin "7") (pinfunction "AUX_CL_7") (pintype "unspecified+no_connect"))
    )
    (net (code "72") (name "unconnected-(U11-AUX_DA-Pad6)") (class "Default")
      (node (ref "U11") (pin "6") (pinfunction "AUX_DA_6") (pintype "unspecified+no_connect"))
    )
    (net (code "73") (name "unconnected-(U11-EP-Pad25)") (class "Default")
      (node (ref "U11") (pin "25") (pinfunction "EP_25") (pintype "unspecified"))
    )
    (net (code "74") (name "unconnected-(U11-INT-Pad12)") (class "Default")
      (node (ref "U11") (pin "12") (pinfunction "INT_12") (pintype "unspecified+no_connect"))
    )
    (net (code "75") (name "unconnected-(U11-NC-Pad2)") (class "Default")
      (node (ref "U11") (pin "2") (pinfunction "NC_2") (pintype "unspecified+no_connect"))
    )
    (net (code "76") (name "unconnected-(U11-NC-Pad3)") (class "Default")
      (node (ref "U11") (pin "3") (pinfunction "NC_3") (pintype "unspecified+no_connect"))
    )
    (net (code "77") (name "unconnected-(U11-NC-Pad4)") (class "Default")
      (node (ref "U11") (pin "4") (pinfunction "NC_4") (pintype "unspecified+no_connect"))
    )
    (net (code "78") (name "unconnected-(U11-NC-Pad5)") (class "Default")
      (node (ref "U11") (pin "5") (pinfunction "NC_5") (pintype "unspecified+no_connect"))
    )
    (net (code "79") (name "unconnected-(U11-NC-Pad14)") (class "Default")
      (node (ref "U11") (pin "14") (pinfunction "NC_14") (pintype "unspecified+no_connect"))
    )
    (net (code "80") (name "unconnected-(U11-NC-Pad15)") (class "Default")
      (node (ref "U11") (pin "15") (pinfunction "NC_15") (pintype "unspecified+no_connect"))
    )
    (net (code "81") (name "unconnected-(U11-NC-Pad16)") (class "Default")
      (node (ref "U11") (pin "16") (pinfunction "NC_16") (pintype "unspecified+no_connect"))
    )
    (net (code "82") (name "unconnected-(U11-NC-Pad17)") (class "Default")
      (node (ref "U11") (pin "17") (pinfunction "NC_17") (pintype "unspecified+no_connect"))
    )
    (net (code "83") (name "unconnected-(U11-RESV-Pad19)") (class "Default")
      (node (ref "U11") (pin "19") (pinfunction "RESV_19") (pintype "unspecified+no_connect"))
    )
    (net (code "84") (name "unconnected-(U11-RESV-Pad21)") (class "Default")
      (node (ref "U11") (pin "21") (pinfunction "RESV_21") (pintype "unspecified+no_connect"))
    )
    (net (code "85") (name "unconnected-(U11-RESV-Pad22)") (class "Default")
      (node (ref "U11") (pin "22") (pinfunction "RESV_22") (pintype "unspecified+no_connect"))
    )
    (net (code "86") (name "unconnected-(U12-NC-Pad4)") (class "Default")
      (node (ref "U12") (pin "4") (pinfunction "NC_4") (pintype "unspecified+no_connect"))
    )
    (net (code "87") (name "unconnected-(U17-NC-Pad4)") (class "Default")
      (node (ref "U17") (pin "4") (pinfunction "NC_4") (pintype "unspecified+no_connect"))
    )
    (net (code "88") (name "unconnected-(U19-Pad1)") (class "Default")
      (node (ref "U19") (pin "1") (pinfunction "1_1") (pintype "unspecified+no_connect"))
    )
  )
)
